# design.net
KiCad netlist of a schematic drawn in Altium Designer
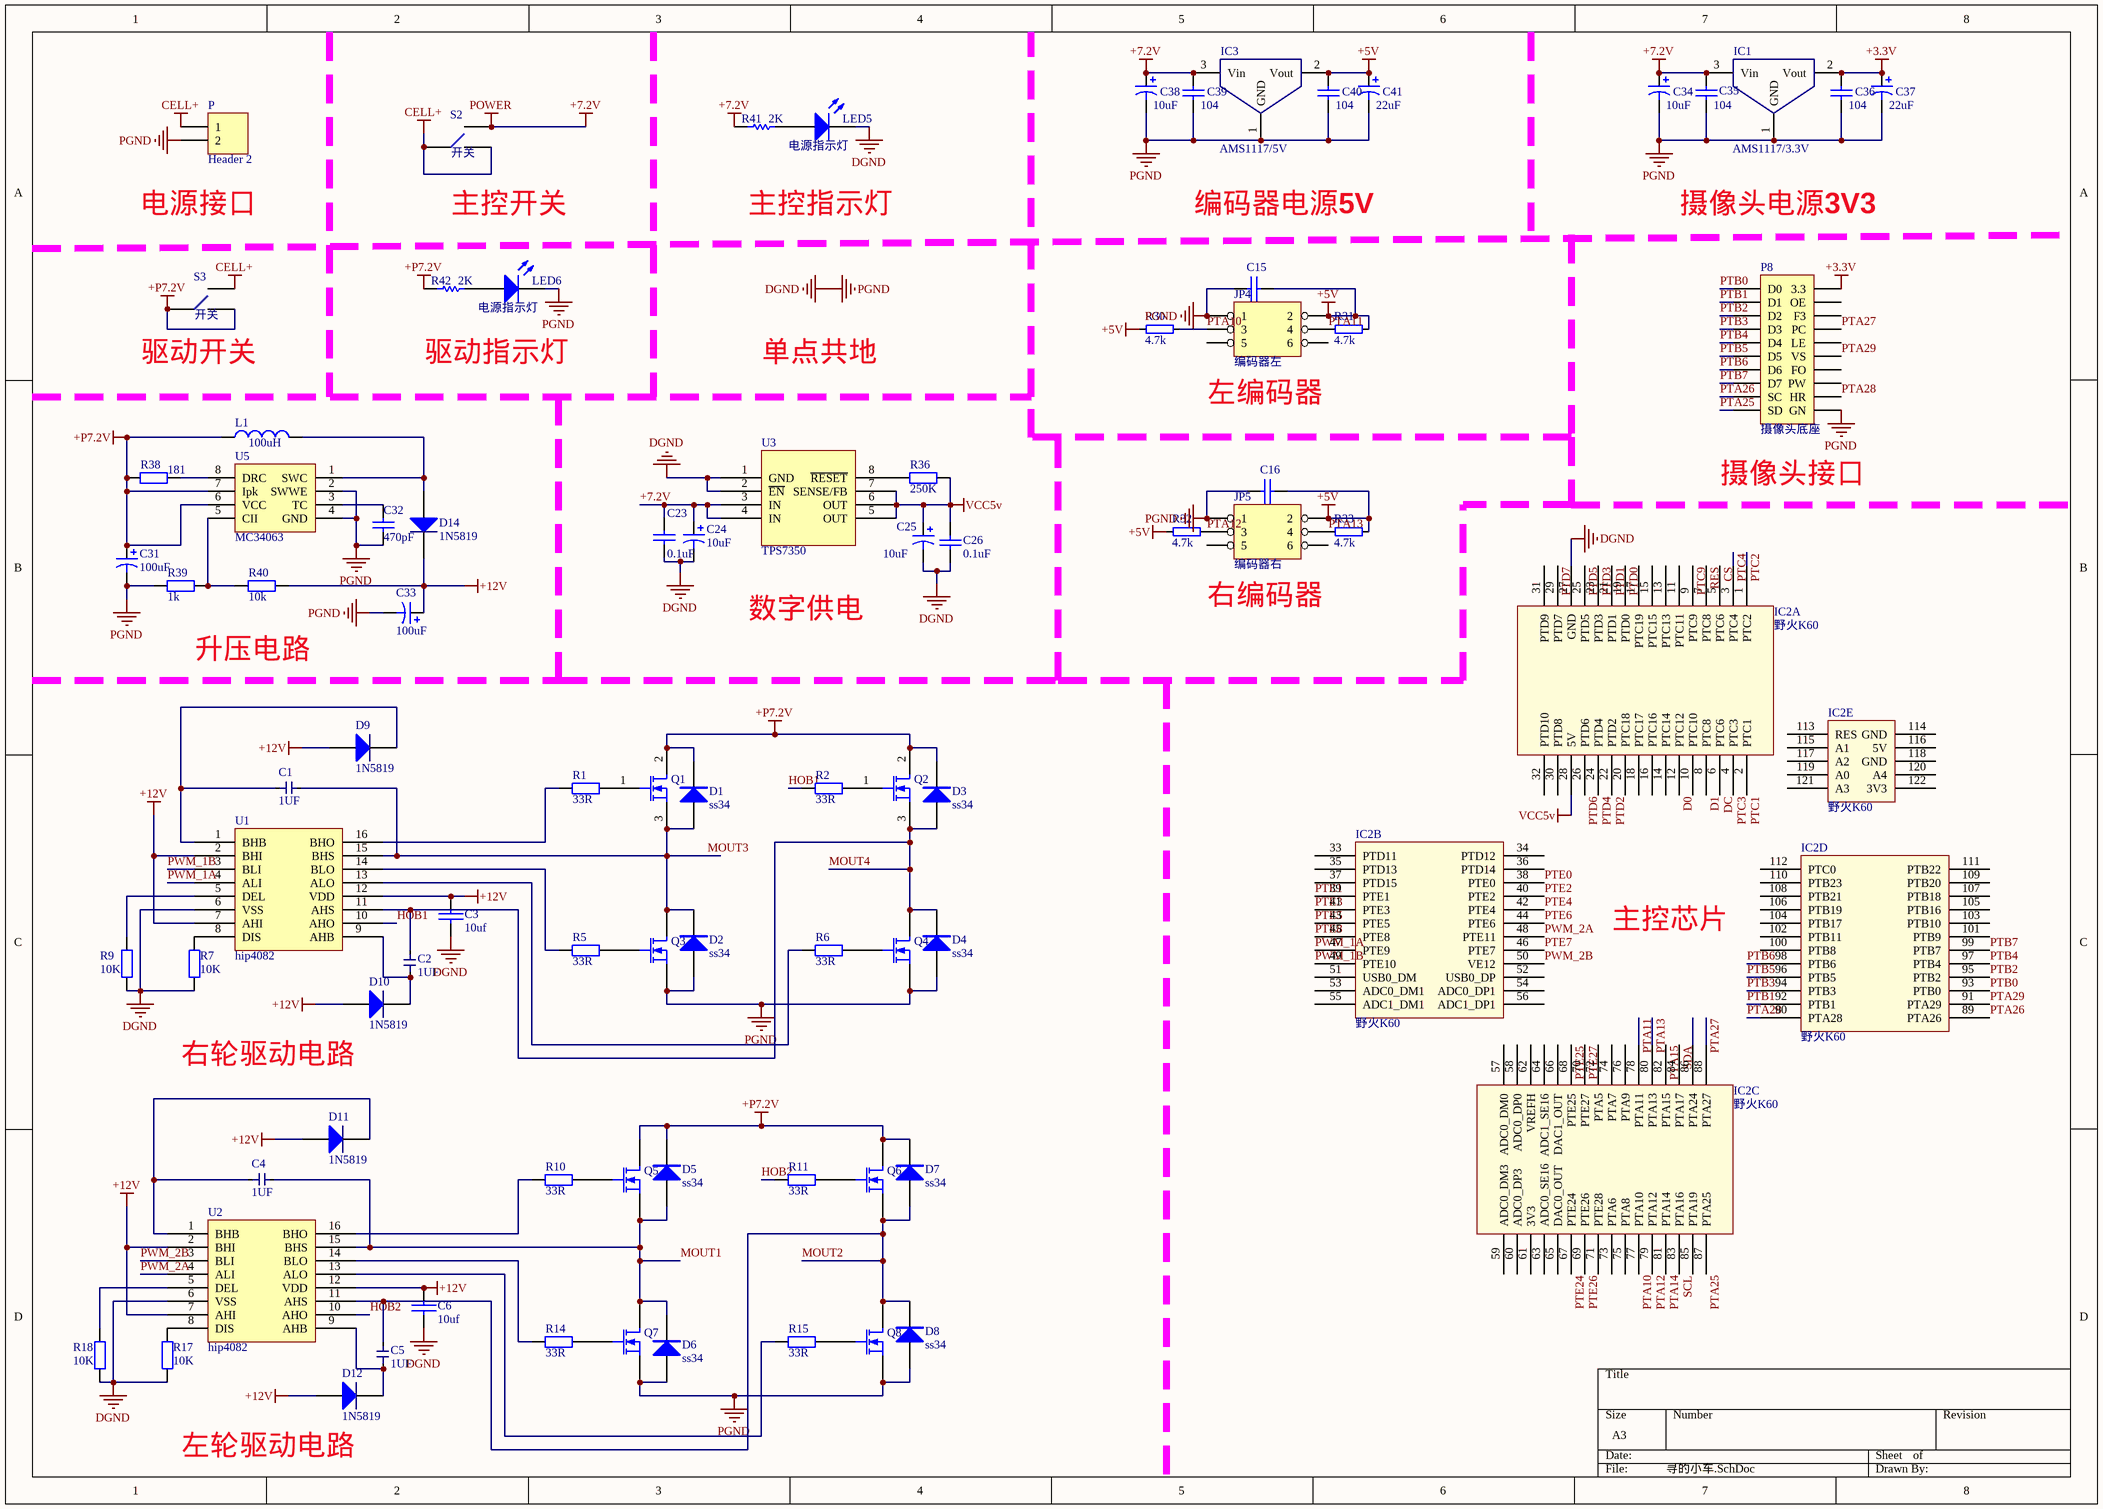
[diagram p0: 寻的小车.SchDoc]

(export (version "E")
  (design (tool "Eeschema 10.0.6"))
  (components
    (comp (ref "C1") (value "1UF") (footprint "0805") (libsource (lib "dx原理图库") (part "电容")))
    (comp (ref "C2") (value "1UF") (footprint "0805") (libsource (lib "dx原理图库") (part "电容")))
    (comp (ref "C3")
      (value "10uf")
      (footprint "0805")
      (description "Capacitor")
      (libsource (lib "电容") (part "普通电容"))
    )
    (comp (ref "C4") (value "1UF") (footprint "0805") (libsource (lib "dx原理图库") (part "电容")))
    (comp (ref "C5") (value "1UF") (footprint "0805") (libsource (lib "dx原理图库") (part "电容")))
    (comp (ref "C6")
      (value "10uf")
      (footprint "0805")
      (description "Capacitor")
      (libsource (lib "电容") (part "普通电容"))
    )
    (comp (ref "C15")
      (value "104")
      (footprint "R0603")
      (description "Capacitor")
      (libsource (lib "电容") (part "普通电容"))
    )
    (comp (ref "C16")
      (value "104")
      (footprint "R0603")
      (description "Capacitor")
      (libsource (lib "电容") (part "普通电容"))
    )
    (comp (ref "C23")
      (value "0.1uF")
      (footprint "R0603")
      (fields (field (name "Comment") "CAPACITY"))
      (libsource (lib "Luo") (part "CAP_0603"))
    )
    (comp (ref "C24")
      (value "10uF")
      (footprint "0805")
      (description "Polarized Capacitor (Surface Mount)")
      (fields (field (name "Comment") "Cap Pol3") (field (name "PUBLISHER") "Altium Limited"))
      (libsource (lib "Miscellaneous Devices") (part "Cap Pol3"))
    )
    (comp (ref "C25")
      (value "10uF")
      (footprint "1206C")
      (fields (field (name "Comment") "CAP  Pol"))
      (libsource (lib "Luo") (part "CAP  Pol"))
    )
    (comp (ref "C26")
      (value "0.1uF")
      (footprint "R0603")
      (fields (field (name "Comment") "CAPACITY"))
      (libsource (lib "Luo") (part "CAP_0603"))
    )
    (comp (ref "C31")
      (value "100uF")
      (footprint "10UF")
      (fields (field (name "Comment") "CAP  Pol"))
      (libsource (lib "Luo") (part "CAP  Pol"))
    )
    (comp (ref "C32")
      (value "470pF")
      (footprint "0805小贴片")
      (fields (field (name "Comment") "CAPACITY"))
      (libsource (lib "Luo") (part "CAP_0805"))
    )
    (comp (ref "C33")
      (value "100uF")
      (footprint "2512")
      (fields (field (name "Comment") "CAP  Pol"))
      (libsource (lib "Luo") (part "CAP  Pol"))
    )
    (comp (ref "C34")
      (value "10uF")
      (footprint "0805")
      (description "Polarized Capacitor (Radial)")
      (fields (field (name "Comment") "Cap Pol1") (field (name "PUBLISHER") "Altium Limited"))
      (libsource (lib "Miscellaneous Devices") (part "Cap Pol1"))
    )
    (comp (ref "C35")
      (value "104")
      (footprint "CAP_0805")
      (description "Capacitor")
      (fields (field (name "Comment") "Cap") (field (name "PUBLISHER") "Altium Limited"))
      (libsource (lib "Miscellaneous Devices") (part "Cap"))
    )
    (comp (ref "C36")
      (value "104")
      (footprint "CAP_0805")
      (description "Capacitor")
      (fields (field (name "Comment") "Cap") (field (name "PUBLISHER") "Altium Limited"))
      (libsource (lib "Miscellaneous Devices") (part "Cap"))
    )
    (comp (ref "C37")
      (value "22uF")
      (footprint "1206C")
      (description "Polarized Capacitor (Radial)")
      (fields (field (name "Comment") "Cap Pol1") (field (name "PUBLISHER") "Altium Limited"))
      (libsource (lib "Miscellaneous Devices") (part "Cap Pol1"))
    )
    (comp (ref "C38")
      (value "10uF")
      (footprint "0805")
      (description "Polarized Capacitor (Radial)")
      (fields (field (name "Comment") "Cap Pol1") (field (name "PUBLISHER") "Altium Limited"))
      (libsource (lib "Miscellaneous Devices") (part "Cap Pol1"))
    )
    (comp (ref "C39")
      (value "104")
      (footprint "CAP_0805")
      (description "Capacitor")
      (fields (field (name "Comment") "Cap") (field (name "PUBLISHER") "Altium Limited"))
      (libsource (lib "Miscellaneous Devices") (part "Cap"))
    )
    (comp (ref "C40")
      (value "104")
      (footprint "CAP_0805")
      (description "Capacitor")
      (fields (field (name "Comment") "Cap") (field (name "PUBLISHER") "Altium Limited"))
      (libsource (lib "Miscellaneous Devices") (part "Cap"))
    )
    (comp (ref "C41")
      (value "22uF")
      (footprint "1206C")
      (description "Polarized Capacitor (Radial)")
      (fields (field (name "Comment") "Cap Pol1") (field (name "PUBLISHER") "Altium Limited"))
      (libsource (lib "Miscellaneous Devices") (part "Cap Pol1"))
    )
    (comp (ref "D1") (value "ss34") (footprint "SS14") (libsource (lib "常用元件库") (part "DIODE")))
    (comp (ref "D2") (value "ss34") (footprint "SS14") (libsource (lib "常用元件库") (part "DIODE")))
    (comp (ref "D3") (value "ss34") (footprint "SS14") (libsource (lib "常用元件库") (part "DIODE")))
    (comp (ref "D4") (value "ss34") (footprint "SS14") (libsource (lib "常用元件库") (part "DIODE")))
    (comp (ref "D5") (value "ss34") (footprint "SS14") (libsource (lib "常用元件库") (part "DIODE")))
    (comp (ref "D6") (value "ss34") (footprint "SS14") (libsource (lib "常用元件库") (part "DIODE")))
    (comp (ref "D7") (value "ss34") (footprint "SS14") (libsource (lib "常用元件库") (part "DIODE")))
    (comp (ref "D8") (value "ss34") (footprint "SS14") (libsource (lib "常用元件库") (part "DIODE")))
    (comp (ref "D9") (value "1N5819") (footprint "SS14") (libsource (lib "Luo") (part "1N5819")))
    (comp (ref "D10") (value "1N5819") (footprint "SS14") (libsource (lib "Luo") (part "1N5819")))
    (comp (ref "D11") (value "1N5819") (footprint "SS14") (libsource (lib "Luo") (part "1N5819")))
    (comp (ref "D12") (value "1N5819") (footprint "SS14") (libsource (lib "Luo") (part "1N5819")))
    (comp (ref "D14") (value "1N5819") (footprint "SS14") (libsource (lib "Luo") (part "1N5819")))
    (comp (ref "IC1")
      (value "AMS1117/3.3V")
      (footprint "SOT_223")
      (libsource (lib "Power_IC") (part "AMS1117"))
    )
    (comp (ref "IC2") (value "野火K60") (footprint "mk60FN") (libsource (lib "Mcu_IC") (part "野火K60")))
    (comp (ref "IC3")
      (value "AMS1117/5V")
      (footprint "SOT_223")
      (libsource (lib "Power_IC") (part "AMS1117"))
    )
    (comp (ref "JP4") (value "编码器左") (footprint "HDR2X3") (libsource (lib "杂元件库") (part "HEADER 3X2")))
    (comp (ref "JP5") (value "编码器右") (footprint "HDR2X3") (libsource (lib "杂元件库") (part "HEADER 3X2")))
    (comp (ref "L1")
      (value "100uH")
      (footprint "小贴片电感")
      (description "Inductor")
      (fields (field (name "PUBLISHER") "Altium Limited"))
      (libsource (lib "Luo") (part "Inductor"))
    )
    (comp (ref "LED5")
      (value "电源指示灯")
      (footprint "0603D")
      (description "Typical INFRARED GaAs LED")
      (fields (field (name "PUBLISHER") "Altium Limited"))
      (libsource (lib "Miscellaneous Devices") (part "LED0"))
    )
    (comp (ref "LED6")
      (value "电源指示灯")
      (footprint "0603D")
      (description "Typical INFRARED GaAs LED")
      (fields (field (name "PUBLISHER") "Altium Limited"))
      (libsource (lib "Miscellaneous Devices") (part "LED0"))
    )
    (comp (ref "P")
      (value "Header 2")
      (footprint "T(G)")
      (description "Header, 2-Pin")
      (fields (field (name "PUBLISHER") "Altium Limited"))
      (libsource (lib "Miscellaneous Connectors") (part "Header 2"))
    )
    (comp (ref "P8")
      (value "摄像头底座")
      (footprint "摄像头座")
      (description "Header, 10-Pin, Dual row, Right Angle")
      (fields (field (name "PUBLISHER") "Altium Limited"))
      (libsource (lib "Miscellaneous Connectors") (part "Header 10X2H"))
    )
    (comp (ref "Q1")
      (value "~")
      (footprint "NMOS")
      (description "N-Channel MOSFET")
      (fields (field (name "PUBLISHER") "Altium Limited"))
      (libsource (lib "Luo") (part "MOSFET-N"))
    )
    (comp (ref "Q2")
      (value "IRF3205")
      (footprint "NMOS")
      (description "N-Channel MOSFET")
      (fields (field (name "PUBLISHER") "Altium Limited"))
      (libsource (lib "Luo") (part "MOSFET-N"))
    )
    (comp (ref "Q3")
      (value "IRF3205")
      (footprint "NMOS")
      (description "N-Channel MOSFET")
      (fields (field (name "PUBLISHER") "Altium Limited"))
      (libsource (lib "") (part "MOSFET-N_1"))
    )
    (comp (ref "Q4")
      (value "IRF3205")
      (footprint "NMOS")
      (description "N-Channel MOSFET")
      (fields (field (name "PUBLISHER") "Altium Limited"))
      (libsource (lib "") (part "MOSFET-N_1"))
    )
    (comp (ref "Q5")
      (value "IRF3205")
      (footprint "NMOS")
      (description "N-Channel MOSFET")
      (fields (field (name "PUBLISHER") "Altium Limited"))
      (libsource (lib "") (part "MOSFET-N_1"))
    )
    (comp (ref "Q6")
      (value "IRF3205")
      (footprint "NMOS")
      (description "N-Channel MOSFET")
      (fields (field (name "PUBLISHER") "Altium Limited"))
      (libsource (lib "") (part "MOSFET-N_1"))
    )
    (comp (ref "Q7")
      (value "IRF3205")
      (footprint "NMOS")
      (description "N-Channel MOSFET")
      (fields (field (name "PUBLISHER") "Altium Limited"))
      (libsource (lib "") (part "MOSFET-N_1"))
    )
    (comp (ref "Q8")
      (value "IRF3205")
      (footprint "NMOS")
      (description "N-Channel MOSFET")
      (fields (field (name "PUBLISHER") "Altium Limited"))
      (libsource (lib "") (part "MOSFET-N_1"))
    )
    (comp (ref "R1")
      (value "33R")
      (footprint "0805")
      (fields (field (name "Comment") "RES2_0805"))
      (libsource (lib "Luo") (part "RES2_0805"))
    )
    (comp (ref "R2")
      (value "33R")
      (footprint "0805")
      (fields (field (name "Comment") "RES2_0805"))
      (libsource (lib "Luo") (part "RES2_0805"))
    )
    (comp (ref "R5")
      (value "33R")
      (footprint "0805")
      (fields (field (name "Comment") "RES2_0805"))
      (libsource (lib "Luo") (part "RES2_0805"))
    )
    (comp (ref "R6")
      (value "33R")
      (footprint "0805")
      (fields (field (name "Comment") "RES2_0805"))
      (libsource (lib "Luo") (part "RES2_0805"))
    )
    (comp (ref "R7")
      (value "10K")
      (footprint "R0603")
      (fields (field (name "Comment") "RES2_0805"))
      (libsource (lib "") (part "RES2_0805_1"))
    )
    (comp (ref "R9")
      (value "10K")
      (footprint "R0603")
      (fields (field (name "Comment") "RES2_0603"))
      (libsource (lib "Luo") (part "RES2_0603"))
    )
    (comp (ref "R10")
      (value "33R")
      (footprint "0805")
      (fields (field (name "Comment") "RES2_0805"))
      (libsource (lib "Luo") (part "RES2_0805"))
    )
    (comp (ref "R11")
      (value "33R")
      (footprint "0805")
      (fields (field (name "Comment") "RES2_0805"))
      (libsource (lib "Luo") (part "RES2_0805"))
    )
    (comp (ref "R14")
      (value "33R")
      (footprint "0805")
      (fields (field (name "Comment") "RES2_0805"))
      (libsource (lib "Luo") (part "RES2_0805"))
    )
    (comp (ref "R15")
      (value "33R")
      (footprint "0805")
      (fields (field (name "Comment") "RES2_0805"))
      (libsource (lib "Luo") (part "RES2_0805"))
    )
    (comp (ref "R17")
      (value "10K")
      (footprint "R0603")
      (fields (field (name "Comment") "RES2_0805"))
      (libsource (lib "") (part "RES2_0805_1"))
    )
    (comp (ref "R18")
      (value "10K")
      (footprint "R0603")
      (fields (field (name "Comment") "RES2_0603"))
      (libsource (lib "Luo") (part "RES2_0603"))
    )
    (comp (ref "R30") (value "4.7k") (footprint "R0603") (libsource (lib "电阻") (part "RES")))
    (comp (ref "R31") (value "4.7k") (footprint "R0603") (libsource (lib "电阻") (part "RES")))
    (comp (ref "R32") (value "4.7k") (footprint "R0603") (libsource (lib "电阻") (part "RES")))
    (comp (ref "R33") (value "4.7k") (footprint "R0603") (libsource (lib "电阻") (part "RES")))
    (comp (ref "R36")
      (value "250K")
      (footprint "0805")
      (fields (field (name "Comment") "RES2_0805"))
      (libsource (lib "Luo") (part "RES2_0805"))
    )
    (comp (ref "R38")
      (value "181")
      (footprint "R0603")
      (fields (field (name "Comment") "RES2_0805"))
      (libsource (lib "Luo") (part "RES2_0805"))
    )
    (comp (ref "R39")
      (value "1k")
      (footprint "R0603")
      (fields (field (name "Comment") "RES2_0805"))
      (libsource (lib "Luo") (part "RES2_0805"))
    )
    (comp (ref "R40")
      (value "10k")
      (footprint "R0603")
      (fields (field (name "Comment") "RES2_0805"))
      (libsource (lib "") (part "RES2_0805_2"))
    )
    (comp (ref "R41")
      (value "2K")
      (footprint "RES_0805")
      (description "Resistor")
      (fields (field (name "Comment") "Res1") (field (name "PUBLISHER") "Altium Limited"))
      (libsource (lib "Miscellaneous Devices") (part "Res1"))
    )
    (comp (ref "R42")
      (value "2K")
      (footprint "RES_0805")
      (description "Resistor")
      (fields (field (name "Comment") "Res1") (field (name "PUBLISHER") "Altium Limited"))
      (libsource (lib "Miscellaneous Devices") (part "Res1"))
    )
    (comp (ref "S2") (value "开关") (footprint "扭头开关") (libsource (lib "lr7843_new") (part "slide_switch")))
    (comp (ref "S3") (value "开关") (footprint "扭头开关") (libsource (lib "lr7843_new") (part "slide_switch")))
    (comp (ref "U1") (value "hip4082") (footprint "SO16NB") (libsource (lib "dx原理图库") (part "hip4082")))
    (comp (ref "U2") (value "hip4082") (footprint "SO16NB") (libsource (lib "dx原理图库") (part "hip4082")))
    (comp (ref "U3")
      (value "TPS7350")
      (footprint "SOP_8")
      (description "This is a power comnonet")
      (libsource (lib "LFB") (part "TPS7350"))
    )
    (comp (ref "U5") (value "MC34063") (footprint "SO8") (libsource (lib "Luo") (part "MC34063")))
  )
  (nets
    (net (code "1") (name "+3.3V") (class "Default")
      (node (ref "C36") (pin "2") (pinfunction "2_2") (pintype "passive"))
      (node (ref "C37") (pin "1") (pinfunction "1_1") (pintype "passive"))
      (node (ref "IC1") (pin "2") (pinfunction "Vout_2") (pintype "passive"))
      (node (ref "P8") (pin "2") (pinfunction "3.3_2") (pintype "passive"))
    )
    (net (code "2") (name "+5V") (class "Default")
      (node (ref "C15") (pin "2") (pinfunction "2_2") (pintype "passive"))
      (node (ref "C16") (pin "2") (pinfunction "2_2") (pintype "passive"))
      (node (ref "C40") (pin "2") (pinfunction "2_2") (pintype "passive"))
      (node (ref "C41") (pin "1") (pinfunction "1_1") (pintype "passive"))
      (node (ref "IC3") (pin "2") (pinfunction "Vout_2") (pintype "passive"))
      (node (ref "JP4") (pin "2") (pinfunction "2_2") (pintype "passive"))
      (node (ref "JP5") (pin "2") (pinfunction "2_2") (pintype "passive"))
      (node (ref "R30") (pin "1") (pinfunction "1_1") (pintype "passive"))
      (node (ref "R31") (pin "2") (pinfunction "2_2") (pintype "passive"))
      (node (ref "R32") (pin "1") (pinfunction "1_1") (pintype "passive"))
      (node (ref "R33") (pin "2") (pinfunction "2_2") (pintype "passive"))
    )
    (net (code "3") (name "+7.2V") (class "Default")
      (node (ref "C23") (pin "2") (pinfunction "2_2") (pintype "passive"))
      (node (ref "C24") (pin "1") (pinfunction "1_1") (pintype "passive"))
      (node (ref "C34") (pin "1") (pinfunction "1_1") (pintype "passive"))
      (node (ref "C35") (pin "2") (pinfunction "2_2") (pintype "passive"))
      (node (ref "C38") (pin "1") (pinfunction "1_1") (pintype "passive"))
      (node (ref "C39") (pin "2") (pinfunction "2_2") (pintype "passive"))
      (node (ref "IC1") (pin "3") (pinfunction "Vin_3") (pintype "passive"))
      (node (ref "IC3") (pin "3") (pinfunction "Vin_3") (pintype "passive"))
      (node (ref "R41") (pin "2") (pinfunction "2_2") (pintype "passive"))
      (node (ref "S2") (pin "2") (pinfunction "2_2") (pintype "passive"))
      (node (ref "U3") (pin "3") (pinfunction "IN_3") (pintype "passive"))
      (node (ref "U3") (pin "4") (pinfunction "IN_4") (pintype "passive"))
    )
    (net (code "4") (name "+12V") (class "Default")
      (node (ref "C3") (pin "1") (pinfunction "1_1") (pintype "passive"))
      (node (ref "C33") (pin "1") (pinfunction "1_1") (pintype "passive"))
      (node (ref "C6") (pin "1") (pinfunction "1_1") (pintype "passive"))
      (node (ref "D10") (pin "1") (pinfunction "A_1") (pintype "passive"))
      (node (ref "D11") (pin "1") (pinfunction "A_1") (pintype "passive"))
      (node (ref "D12") (pin "1") (pinfunction "A_1") (pintype "passive"))
      (node (ref "D14") (pin "2") (pinfunction "K_2") (pintype "passive"))
      (node (ref "D9") (pin "1") (pinfunction "A_1") (pintype "passive"))
      (node (ref "R40") (pin "1") (pinfunction "1_1") (pintype "passive"))
      (node (ref "U1") (pin "12") (pinfunction "VDD_12") (pintype "passive"))
      (node (ref "U1") (pin "2") (pinfunction "BHI_2") (pintype "passive"))
      (node (ref "U1") (pin "7") (pinfunction "AHI_7") (pintype "passive"))
      (node (ref "U2") (pin "12") (pinfunction "VDD_12") (pintype "passive"))
      (node (ref "U2") (pin "2") (pinfunction "BHI_2") (pintype "passive"))
      (node (ref "U2") (pin "7") (pinfunction "AHI_7") (pintype "passive"))
    )
    (net (code "5") (name "+P7.2V") (class "Default")
      (node (ref "C31") (pin "1") (pinfunction "1_1") (pintype "passive"))
      (node (ref "D1") (pin "K") (pinfunction "K_K") (pintype "passive"))
      (node (ref "D3") (pin "K") (pinfunction "K_K") (pintype "passive"))
      (node (ref "D5") (pin "K") (pinfunction "K_K") (pintype "passive"))
      (node (ref "D7") (pin "K") (pinfunction "K_K") (pintype "passive"))
      (node (ref "L1") (pin "1") (pinfunction "1_1") (pintype "passive"))
      (node (ref "Q1") (pin "2") (pinfunction "D_2") (pintype "passive"))
      (node (ref "Q2") (pin "2") (pinfunction "D_2") (pintype "passive"))
      (node (ref "Q5") (pin "2") (pinfunction "D_2") (pintype "passive"))
      (node (ref "Q6") (pin "2") (pinfunction "D_2") (pintype "passive"))
      (node (ref "R38") (pin "1") (pinfunction "1_1") (pintype "passive"))
      (node (ref "R42") (pin "2") (pinfunction "2_2") (pintype "passive"))
      (node (ref "S3") (pin "1") (pinfunction "1_1") (pintype "passive"))
      (node (ref "S3") (pin "3") (pinfunction "3_3") (pintype "passive"))
      (node (ref "U5") (pin "6") (pinfunction "VCC_6") (pintype "passive"))
      (node (ref "U5") (pin "7") (pinfunction "Ipk_7") (pintype "passive"))
    )
    (net (code "6") (name "/CS") (class "Default")
      (node (ref "IC2") (pin "5") (pinfunction "PTC6_5") (pintype "passive"))
    )
    (net (code "7") (name "/D0") (class "Default")
      (node (ref "IC2") (pin "12") (pinfunction "PTC12_12") (pintype "passive"))
    )
    (net (code "8") (name "/D1") (class "Default")
      (node (ref "IC2") (pin "8") (pinfunction "PTC8_8") (pintype "passive"))
    )
    (net (code "9") (name "/DC") (class "Default")
      (node (ref "IC2") (pin "6") (pinfunction "PTC6_6") (pintype "passive"))
    )
    (net (code "10") (name "/HOB1") (class "Default")
      (node (ref "R2") (pin "1") (pinfunction "1_1") (pintype "passive"))
      (node (ref "U1") (pin "10") (pinfunction "AHO_10") (pintype "passive"))
    )
    (net (code "11") (name "/HOB2") (class "Default")
      (node (ref "R11") (pin "1") (pinfunction "1_1") (pintype "passive"))
      (node (ref "U2") (pin "10") (pinfunction "AHO_10") (pintype "passive"))
    )
    (net (code "12") (name "/MOUT1") (class "Default")
      (node (ref "C4") (pin "18") (pinfunction "18_18") (pintype "passive"))
      (node (ref "D5") (pin "A") (pinfunction "A_A") (pintype "passive"))
      (node (ref "D6") (pin "K") (pinfunction "K_K") (pintype "passive"))
      (node (ref "Q5") (pin "3") (pinfunction "S_3") (pintype "passive"))
      (node (ref "Q7") (pin "2") (pinfunction "D_2") (pintype "passive"))
      (node (ref "U2") (pin "15") (pinfunction "BHS_15") (pintype "passive"))
    )
    (net (code "13") (name "/MOUT2") (class "Default")
      (node (ref "C5") (pin "18") (pinfunction "18_18") (pintype "passive"))
      (node (ref "D7") (pin "A") (pinfunction "A_A") (pintype "passive"))
      (node (ref "D8") (pin "K") (pinfunction "K_K") (pintype "passive"))
      (node (ref "Q6") (pin "3") (pinfunction "S_3") (pintype "passive"))
      (node (ref "Q8") (pin "2") (pinfunction "D_2") (pintype "passive"))
      (node (ref "U2") (pin "11") (pinfunction "AHS_11") (pintype "passive"))
    )
    (net (code "14") (name "/MOUT3") (class "Default")
      (node (ref "C1") (pin "18") (pinfunction "18_18") (pintype "passive"))
      (node (ref "D1") (pin "A") (pinfunction "A_A") (pintype "passive"))
      (node (ref "D2") (pin "K") (pinfunction "K_K") (pintype "passive"))
      (node (ref "Q1") (pin "3") (pinfunction "S_3") (pintype "passive"))
      (node (ref "Q3") (pin "2") (pinfunction "D_2") (pintype "passive"))
      (node (ref "U1") (pin "15") (pinfunction "BHS_15") (pintype "passive"))
    )
    (net (code "15") (name "/MOUT4") (class "Default")
      (node (ref "C2") (pin "18") (pinfunction "18_18") (pintype "passive"))
      (node (ref "D3") (pin "A") (pinfunction "A_A") (pintype "passive"))
      (node (ref "D4") (pin "K") (pinfunction "K_K") (pintype "passive"))
      (node (ref "Q2") (pin "3") (pinfunction "S_3") (pintype "passive"))
      (node (ref "Q4") (pin "2") (pinfunction "D_2") (pintype "passive"))
      (node (ref "U1") (pin "11") (pinfunction "AHS_11") (pintype "passive"))
    )
    (net (code "16") (name "/PTA10") (class "Default")
      (node (ref "IC2") (pin "77") (pinfunction "PTA10_77") (pintype "passive"))
      (node (ref "JP4") (pin "3") (pinfunction "3_3") (pintype "passive"))
      (node (ref "R30") (pin "2") (pinfunction "2_2") (pintype "passive"))
    )
    (net (code "17") (name "/PTA11") (class "Default")
      (node (ref "IC2") (pin "78") (pinfunction "PTA11_78") (pintype "passive"))
      (node (ref "JP4") (pin "4") (pinfunction "4_4") (pintype "passive"))
      (node (ref "R31") (pin "1") (pinfunction "1_1") (pintype "passive"))
    )
    (net (code "18") (name "/PTA12") (class "Default")
      (node (ref "IC2") (pin "79") (pinfunction "PTA12_79") (pintype "passive"))
      (node (ref "JP5") (pin "3") (pinfunction "3_3") (pintype "passive"))
      (node (ref "R32") (pin "2") (pinfunction "2_2") (pintype "passive"))
    )
    (net (code "19") (name "/PTA13") (class "Default")
      (node (ref "IC2") (pin "80") (pinfunction "PTA13_80") (pintype "passive"))
      (node (ref "JP5") (pin "4") (pinfunction "4_4") (pintype "passive"))
      (node (ref "R33") (pin "1") (pinfunction "1_1") (pintype "passive"))
    )
    (net (code "20") (name "/PTA14") (class "Default")
      (node (ref "IC2") (pin "81") (pinfunction "PTA14_81") (pintype "passive"))
    )
    (net (code "21") (name "/PTA15") (class "Default")
      (node (ref "IC2") (pin "82") (pinfunction "PTA15_82") (pintype "passive"))
    )
    (net (code "22") (name "/PTA25") (class "Default")
      (node (ref "IC2") (pin "87") (pinfunction "PTA25_87") (pintype "passive"))
      (node (ref "P8") (pin "19") (pinfunction "SD_19") (pintype "passive"))
    )
    (net (code "23") (name "/PTA26") (class "Default")
      (node (ref "IC2") (pin "89") (pinfunction "PTA26_89") (pintype "passive"))
      (node (ref "P8") (pin "17") (pinfunction "SC_17") (pintype "passive"))
    )
    (net (code "24") (name "/PTA27") (class "Default")
      (node (ref "IC2") (pin "88") (pinfunction "PTA27_88") (pintype "passive"))
      (node (ref "P8") (pin "8") (pinfunction "PC_8") (pintype "passive"))
    )
    (net (code "25") (name "/PTA28") (class "Default")
      (node (ref "IC2") (pin "90") (pinfunction "PTA28_90") (pintype "passive"))
      (node (ref "P8") (pin "18") (pinfunction "HR_18") (pintype "passive"))
    )
    (net (code "26") (name "/PTA29") (class "Default")
      (node (ref "IC2") (pin "91") (pinfunction "PTA29_91") (pintype "passive"))
      (node (ref "P8") (pin "12") (pinfunction "VS_12") (pintype "passive"))
    )
    (net (code "27") (name "/PTB0") (class "Default")
      (node (ref "IC2") (pin "93") (pinfunction "PTB0_93") (pintype "passive"))
      (node (ref "P8") (pin "1") (pinfunction "D0_1") (pintype "passive"))
    )
    (net (code "28") (name "/PTB1") (class "Default")
      (node (ref "IC2") (pin "92") (pinfunction "PTB1_92") (pintype "passive"))
      (node (ref "P8") (pin "3") (pinfunction "D1_3") (pintype "passive"))
    )
    (net (code "29") (name "/PTB2") (class "Default")
      (node (ref "IC2") (pin "95") (pinfunction "PTB2_95") (pintype "passive"))
      (node (ref "P8") (pin "5") (pinfunction "D2_5") (pintype "passive"))
    )
    (net (code "30") (name "/PTB3") (class "Default")
      (node (ref "IC2") (pin "94") (pinfunction "PTB3_94") (pintype "passive"))
      (node (ref "P8") (pin "7") (pinfunction "D3_7") (pintype "passive"))
    )
    (net (code "31") (name "/PTB4") (class "Default")
      (node (ref "IC2") (pin "97") (pinfunction "PTB4_97") (pintype "passive"))
      (node (ref "P8") (pin "9") (pinfunction "D4_9") (pintype "passive"))
    )
    (net (code "32") (name "/PTB5") (class "Default")
      (node (ref "IC2") (pin "96") (pinfunction "PTB5_96") (pintype "passive"))
      (node (ref "P8") (pin "11") (pinfunction "D5_11") (pintype "passive"))
    )
    (net (code "33") (name "/PTB6") (class "Default")
      (node (ref "IC2") (pin "98") (pinfunction "PTB6_98") (pintype "passive"))
      (node (ref "P8") (pin "13") (pinfunction "D6_13") (pintype "passive"))
    )
    (net (code "34") (name "/PTB7") (class "Default")
      (node (ref "IC2") (pin "99") (pinfunction "PTB7_99") (pintype "passive"))
      (node (ref "P8") (pin "15") (pinfunction "D7_15") (pintype "passive"))
    )
    (net (code "35") (name "/PTC1") (class "Default")
      (node (ref "IC2") (pin "2") (pinfunction "PTC1_2") (pintype "passive"))
    )
    (net (code "36") (name "/PTC2") (class "Default")
      (node (ref "IC2") (pin "1") (pinfunction "PTC2_1") (pintype "passive"))
    )
    (net (code "37") (name "/PTC3") (class "Default")
      (node (ref "IC2") (pin "4") (pinfunction "PTC3_4") (pintype "passive"))
    )
    (net (code "38") (name "/PTC4") (class "Default")
      (node (ref "IC2") (pin "3") (pinfunction "PTC4_3") (pintype "passive"))
    )
    (net (code "39") (name "/PTC9") (class "Default")
      (node (ref "IC2") (pin "9") (pinfunction "PTC9_9") (pintype "passive"))
    )
    (net (code "40") (name "/PTD0") (class "Default")
      (node (ref "IC2") (pin "19") (pinfunction "PTD0_19") (pintype "passive"))
    )
    (net (code "41") (name "/PTD1") (class "Default")
      (node (ref "IC2") (pin "21") (pinfunction "PTD1_21") (pintype "passive"))
    )
    (net (code "42") (name "/PTD2") (class "Default")
      (node (ref "IC2") (pin "22") (pinfunction "PTD2_22") (pintype "passive"))
    )
    (net (code "43") (name "/PTD3") (class "Default")
      (node (ref "IC2") (pin "23") (pinfunction "PTD3_23") (pintype "passive"))
    )
    (net (code "44") (name "/PTD4") (class "Default")
      (node (ref "IC2") (pin "24") (pinfunction "PTD4_24") (pintype "passive"))
    )
    (net (code "45") (name "/PTD5") (class "Default")
      (node (ref "IC2") (pin "25") (pinfunction "PTD5_25") (pintype "passive"))
    )
    (net (code "46") (name "/PTD6") (class "Default")
      (node (ref "IC2") (pin "26") (pinfunction "PTD6_26") (pintype "passive"))
    )
    (net (code "47") (name "/PTD7") (class "Default")
      (node (ref "IC2") (pin "29") (pinfunction "PTD7_29") (pintype "passive"))
    )
    (net (code "48") (name "/PTE0") (class "Default")
      (node (ref "IC2") (pin "38") (pinfunction "PTE0_38") (pintype "passive"))
    )
    (net (code "49") (name "/PTE1") (class "Default")
      (node (ref "IC2") (pin "39") (pinfunction "PTE1_39") (pintype "passive"))
    )
    (net (code "50") (name "/PTE2") (class "Default")
      (node (ref "IC2") (pin "40") (pinfunction "PTE2_40") (pintype "passive"))
    )
    (net (code "51") (name "/PTE3") (class "Default")
      (node (ref "IC2") (pin "41") (pinfunction "PTE3_41") (pintype "passive"))
    )
    (net (code "52") (name "/PTE4") (class "Default")
      (node (ref "IC2") (pin "42") (pinfunction "PTE4_42") (pintype "passive"))
    )
    (net (code "53") (name "/PTE5") (class "Default")
      (node (ref "IC2") (pin "43") (pinfunction "PTE5_43") (pintype "passive"))
    )
    (net (code "54") (name "/PTE6") (class "Default")
      (node (ref "IC2") (pin "44") (pinfunction "PTE6_44") (pintype "passive"))
    )
    (net (code "55") (name "/PTE7") (class "Default")
      (node (ref "IC2") (pin "46") (pinfunction "PTE7_46") (pintype "passive"))
    )
    (net (code "56") (name "/PTE8") (class "Default")
      (node (ref "IC2") (pin "45") (pinfunction "PTE8_45") (pintype "passive"))
    )
    (net (code "57") (name "/PTE24") (class "Default")
      (node (ref "IC2") (pin "67") (pinfunction "PTE24_67") (pintype "passive"))
    )
    (net (code "58") (name "/PTE25") (class "Default")
      (node (ref "IC2") (pin "68") (pinfunction "PTE25_68") (pintype "passive"))
    )
    (net (code "59") (name "/PTE26") (class "Default")
      (node (ref "IC2") (pin "69") (pinfunction "PTE26_69") (pintype "passive"))
    )
    (net (code "60") (name "/PTE27") (class "Default")
      (node (ref "IC2") (pin "70") (pinfunction "PTE27_70") (pintype "passive"))
    )
    (net (code "61") (name "/PWM_1A") (class "Default")
      (node (ref "IC2") (pin "47") (pinfunction "PTE9_47") (pintype "passive"))
      (node (ref "U1") (pin "4") (pinfunction "ALI_4") (pintype "passive"))
    )
    (net (code "62") (name "/PWM_1B") (class "Default")
      (node (ref "IC2") (pin "49") (pinfunction "PTE10_49") (pintype "passive"))
      (node (ref "U1") (pin "3") (pinfunction "BLI_3") (pintype "passive"))
    )
    (net (code "63") (name "/PWM_2A") (class "Default")
      (node (ref "IC2") (pin "48") (pinfunction "PTE11_48") (pintype "passive"))
      (node (ref "U2") (pin "4") (pinfunction "ALI_4") (pintype "passive"))
    )
    (net (code "64") (name "/PWM_2B") (class "Default")
      (node (ref "IC2") (pin "50") (pinfunction "VE12_50") (pintype "passive"))
      (node (ref "U2") (pin "3") (pinfunction "BLI_3") (pintype "passive"))
    )
    (net (code "65") (name "/RES") (class "Default")
      (node (ref "IC2") (pin "7") (pinfunction "PTC8_7") (pintype "passive"))
    )
    (net (code "66") (name "/SCL") (class "Default")
      (node (ref "IC2") (pin "83") (pinfunction "PTA16_83") (pintype "passive"))
    )
    (net (code "67") (name "/SDA") (class "Default")
      (node (ref "IC2") (pin "84") (pinfunction "PTA17_84") (pintype "passive"))
    )
    (net (code "68") (name "CELL+") (class "Default")
      (node (ref "P") (pin "1") (pinfunction "1_1") (pintype "passive"))
      (node (ref "S2") (pin "1") (pinfunction "1_1") (pintype "passive"))
      (node (ref "S2") (pin "3") (pinfunction "3_3") (pintype "passive"))
      (node (ref "S3") (pin "2") (pinfunction "2_2") (pintype "passive"))
    )
    (net (code "69") (name "DGND") (class "Default")
      (node (ref "C15") (pin "1") (pinfunction "1_1") (pintype "passive"))
      (node (ref "C16") (pin "1") (pinfunction "1_1") (pintype "passive"))
      (node (ref "C23") (pin "1") (pinfunction "1_1") (pintype "passive"))
      (node (ref "C24") (pin "2") (pinfunction "2_2") (pintype "passive"))
      (node (ref "C25") (pin "2") (pinfunction "2_2") (pintype "passive"))
      (node (ref "C26") (pin "1") (pinfunction "1_1") (pintype "passive"))
      (node (ref "C3") (pin "2") (pinfunction "2_2") (pintype "passive"))
      (node (ref "C31") (pin "2") (pinfunction "2_2") (pintype "passive"))
      (node (ref "C32") (pin "1") (pinfunction "1_1") (pintype "passive"))
      (node (ref "C33") (pin "2") (pinfunction "2_2") (pintype "passive"))
      (node (ref "C34") (pin "2") (pinfunction "2_2") (pintype "passive"))
      (node (ref "C35") (pin "1") (pinfunction "1_1") (pintype "passive"))
      (node (ref "C36") (pin "1") (pinfunction "1_1") (pintype "passive"))
      (node (ref "C37") (pin "2") (pinfunction "2_2") (pintype "passive"))
      (node (ref "C38") (pin "2") (pinfunction "2_2") (pintype "passive"))
      (node (ref "C39") (pin "1") (pinfunction "1_1") (pintype "passive"))
      (node (ref "C40") (pin "1") (pinfunction "1_1") (pintype "passive"))
      (node (ref "C41") (pin "2") (pinfunction "2_2") (pintype "passive"))
      (node (ref "C6") (pin "2") (pinfunction "2_2") (pintype "passive"))
      (node (ref "D2") (pin "A") (pinfunction "A_A") (pintype "passive"))
      (node (ref "D4") (pin "A") (pinfunction "A_A") (pintype "passive"))
      (node (ref "D6") (pin "A") (pinfunction "A_A") (pintype "passive"))
      (node (ref "D8") (pin "A") (pinfunction "A_A") (pintype "passive"))
      (node (ref "IC1") (pin "1") (pinfunction "GND_1") (pintype "passive"))
      (node (ref "IC2") (pin "27") (pinfunction "GND_27") (pintype "passive"))
      (node (ref "IC3") (pin "1") (pinfunction "GND_1") (pintype "passive"))
      (node (ref "JP4") (pin "1") (pinfunction "1_1") (pintype "passive"))
      (node (ref "JP5") (pin "1") (pinfunction "1_1") (pintype "passive"))
      (node (ref "LED5") (pin "2") (pinfunction "K_2") (pintype "passive"))
      (node (ref "LED6") (pin "2") (pinfunction "K_2") (pintype "passive"))
      (node (ref "P") (pin "2") (pinfunction "2_2") (pintype "passive"))
      (node (ref "P8") (pin "20") (pinfunction "GN_20") (pintype "passive"))
      (node (ref "Q3") (pin "3") (pinfunction "S_3") (pintype "passive"))
      (node (ref "Q4") (pin "3") (pinfunction "S_3") (pintype "passive"))
      (node (ref "Q7") (pin "3") (pinfunction "S_3") (pintype "passive"))
      (node (ref "Q8") (pin "3") (pinfunction "S_3") (pintype "passive"))
      (node (ref "R17") (pin "1") (pinfunction "1_1") (pintype "passive"))
      (node (ref "R18") (pin "2") (pinfunction "2_2") (pintype "passive"))
      (node (ref "R39") (pin "1") (pinfunction "1_1") (pintype "passive"))
      (node (ref "R7") (pin "1") (pinfunction "1_1") (pintype "passive"))
      (node (ref "R9") (pin "2") (pinfunction "2_2") (pintype "passive"))
      (node (ref "U1") (pin "6") (pinfunction "VSS_6") (pintype "passive"))
      (node (ref "U2") (pin "6") (pinfunction "VSS_6") (pintype "passive"))
      (node (ref "U3") (pin "1") (pinfunction "GND_1") (pintype "passive"))
      (node (ref "U3") (pin "2") (pinfunction "~{EN}_2") (pintype "passive"))
      (node (ref "U5") (pin "2") (pinfunction "SWWE_2") (pintype "passive"))
      (node (ref "U5") (pin "4") (pinfunction "GND_4") (pintype "passive"))
    )
    (net (code "70") (name "Net-(D9-K)") (class "Default")
      (node (ref "C1") (pin "17") (pintype "passive"))
      (node (ref "D9") (pin "2") (pinfunction "K_2") (pintype "passive"))
      (node (ref "U1") (pin "1") (pinfunction "BHB_1") (pintype "passive"))
    )
    (net (code "71") (name "Net-(D10-K)") (class "Default")
      (node (ref "C2") (pin "17") (pintype "passive"))
      (node (ref "D10") (pin "2") (pinfunction "K_2") (pintype "passive"))
      (node (ref "U1") (pin "9") (pinfunction "AHB_9") (pintype "passive"))
    )
    (net (code "72") (name "Net-(D11-K)") (class "Default")
      (node (ref "C4") (pin "17") (pintype "passive"))
      (node (ref "D11") (pin "2") (pinfunction "K_2") (pintype "passive"))
      (node (ref "U2") (pin "1") (pinfunction "BHB_1") (pintype "passive"))
    )
    (net (code "73") (name "Net-(D12-K)") (class "Default")
      (node (ref "C5") (pin "17") (pintype "passive"))
      (node (ref "D12") (pin "2") (pinfunction "K_2") (pintype "passive"))
      (node (ref "U2") (pin "9") (pinfunction "AHB_9") (pintype "passive"))
    )
    (net (code "74") (name "Net-(D14-A)") (class "Default")
      (node (ref "D14") (pin "1") (pinfunction "A_1") (pintype "passive"))
      (node (ref "L1") (pin "2") (pinfunction "2_2") (pintype "passive"))
      (node (ref "U5") (pin "1") (pinfunction "SWC_1") (pintype "passive"))
    )
    (net (code "75") (name "Net-(LED5-A)") (class "Default")
      (node (ref "LED5") (pin "1") (pinfunction "A_1") (pintype "passive"))
      (node (ref "R41") (pin "1") (pinfunction "1_1") (pintype "passive"))
    )
    (net (code "76") (name "Net-(LED6-A)") (class "Default")
      (node (ref "LED6") (pin "1") (pinfunction "A_1") (pintype "passive"))
      (node (ref "R42") (pin "1") (pinfunction "1_1") (pintype "passive"))
    )
    (net (code "77") (name "Net-(Q1-G)") (class "Default")
      (node (ref "Q1") (pin "1") (pinfunction "G_1") (pintype "passive"))
      (node (ref "R1") (pin "2") (pinfunction "2_2") (pintype "passive"))
    )
    (net (code "78") (name "Net-(Q2-G)") (class "Default")
      (node (ref "Q2") (pin "1") (pinfunction "G_1") (pintype "passive"))
      (node (ref "R2") (pin "2") (pinfunction "2_2") (pintype "passive"))
    )
    (net (code "79") (name "Net-(Q3-G)") (class "Default")
      (node (ref "Q3") (pin "1") (pinfunction "G_1") (pintype "passive"))
      (node (ref "R5") (pin "2") (pinfunction "2_2") (pintype "passive"))
    )
    (net (code "80") (name "Net-(Q4-G)") (class "Default")
      (node (ref "Q4") (pin "1") (pinfunction "G_1") (pintype "passive"))
      (node (ref "R6") (pin "2") (pinfunction "2_2") (pintype "passive"))
    )
    (net (code "81") (name "Net-(Q5-G)") (class "Default")
      (node (ref "Q5") (pin "1") (pinfunction "G_1") (pintype "passive"))
      (node (ref "R10") (pin "2") (pinfunction "2_2") (pintype "passive"))
    )
    (net (code "82") (name "Net-(Q6-G)") (class "Default")
      (node (ref "Q6") (pin "1") (pinfunction "G_1") (pintype "passive"))
      (node (ref "R11") (pin "2") (pinfunction "2_2") (pintype "passive"))
    )
    (net (code "83") (name "Net-(Q7-G)") (class "Default")
      (node (ref "Q7") (pin "1") (pinfunction "G_1") (pintype "passive"))
      (node (ref "R14") (pin "2") (pinfunction "2_2") (pintype "passive"))
    )
    (net (code "84") (name "Net-(Q8-G)") (class "Default")
      (node (ref "Q8") (pin "1") (pinfunction "G_1") (pintype "passive"))
      (node (ref "R15") (pin "2") (pinfunction "2_2") (pintype "passive"))
    )
    (net (code "85") (name "Net-(U1-ALO)") (class "Default")
      (node (ref "R6") (pin "1") (pinfunction "1_1") (pintype "passive"))
      (node (ref "U1") (pin "13") (pinfunction "ALO_13") (pintype "passive"))
    )
    (net (code "86") (name "Net-(U1-BHO)") (class "Default")
      (node (ref "R1") (pin "1") (pinfunction "1_1") (pintype "passive"))
      (node (ref "U1") (pin "16") (pinfunction "BHO_16") (pintype "passive"))
    )
    (net (code "87") (name "Net-(U1-BLO)") (class "Default")
      (node (ref "R5") (pin "1") (pinfunction "1_1") (pintype "passive"))
      (node (ref "U1") (pin "14") (pinfunction "BLO_14") (pintype "passive"))
    )
    (net (code "88") (name "Net-(U1-DEL)") (class "Default")
      (node (ref "R9") (pin "1") (pinfunction "1_1") (pintype "passive"))
      (node (ref "U1") (pin "5") (pinfunction "DEL_5") (pintype "passive"))
    )
    (net (code "89") (name "Net-(U1-DIS)") (class "Default")
      (node (ref "R7") (pin "2") (pinfunction "2_2") (pintype "passive"))
      (node (ref "U1") (pin "8") (pinfunction "DIS_8") (pintype "passive"))
    )
    (net (code "90") (name "Net-(U2-ALO)") (class "Default")
      (node (ref "R15") (pin "1") (pinfunction "1_1") (pintype "passive"))
      (node (ref "U2") (pin "13") (pinfunction "ALO_13") (pintype "passive"))
    )
    (net (code "91") (name "Net-(U2-BHO)") (class "Default")
      (node (ref "R10") (pin "1") (pinfunction "1_1") (pintype "passive"))
      (node (ref "U2") (pin "16") (pinfunction "BHO_16") (pintype "passive"))
    )
    (net (code "92") (name "Net-(U2-BLO)") (class "Default")
      (node (ref "R14") (pin "1") (pinfunction "1_1") (pintype "passive"))
      (node (ref "U2") (pin "14") (pinfunction "BLO_14") (pintype "passive"))
    )
    (net (code "93") (name "Net-(U2-DEL)") (class "Default")
      (node (ref "R18") (pin "1") (pinfunction "1_1") (pintype "passive"))
      (node (ref "U2") (pin "5") (pinfunction "DEL_5") (pintype "passive"))
    )
    (net (code "94") (name "Net-(U2-DIS)") (class "Default")
      (node (ref "R17") (pin "2") (pinfunction "2_2") (pintype "passive"))
      (node (ref "U2") (pin "8") (pinfunction "DIS_8") (pintype "passive"))
    )
    (net (code "95") (name "Net-(U3-~{RESET})") (class "Default")
      (node (ref "R36") (pin "1") (pinfunction "1_1") (pintype "passive"))
      (node (ref "U3") (pin "8") (pinfunction "~{RESET}_8") (pintype "passive"))
    )
    (net (code "96") (name "Net-(U5-CII)") (class "Default")
      (node (ref "R39") (pin "2") (pinfunction "2_2") (pintype "passive"))
      (node (ref "R40") (pin "2") (pinfunction "2_2") (pintype "passive"))
      (node (ref "U5") (pin "5") (pinfunction "CII_5") (pintype "passive"))
    )
    (net (code "97") (name "Net-(U5-DRC)") (class "Default")
      (node (ref "R38") (pin "2") (pinfunction "2_2") (pintype "passive"))
      (node (ref "U5") (pin "8") (pinfunction "DRC_8") (pintype "passive"))
    )
    (net (code "98") (name "Net-(U5-TC)") (class "Default")
      (node (ref "C32") (pin "2") (pinfunction "2_2") (pintype "passive"))
      (node (ref "U5") (pin "3") (pinfunction "TC_3") (pintype "passive"))
    )
    (net (code "99") (name "VCC5v") (class "Default")
      (node (ref "C25") (pin "1") (pinfunction "1_1") (pintype "passive"))
      (node (ref "C26") (pin "2") (pinfunction "2_2") (pintype "passive"))
      (node (ref "IC2") (pin "28") (pinfunction "5V_28") (pintype "passive"))
      (node (ref "R36") (pin "2") (pinfunction "2_2") (pintype "passive"))
      (node (ref "U3") (pin "5") (pinfunction "OUT_5") (pintype "passive"))
      (node (ref "U3") (pin "6") (pinfunction "OUT_6") (pintype "passive"))
      (node (ref "U3") (pin "7") (pinfunction "SENSE/FB_7") (pintype "passive"))
    )
    (net (code "100") (name "unconnected-(IC2A-PTC10-Pad10)") (class "Default")
      (node (ref "IC2") (pin "10") (pinfunction "PTC10_10") (pintype "passive"))
    )
    (net (code "101") (name "unconnected-(IC2A-PTC11-Pad11)") (class "Default")
      (node (ref "IC2") (pin "11") (pinfunction "PTC11_11") (pintype "passive"))
    )
    (net (code "102") (name "unconnected-(IC2A-PTC13-Pad13)") (class "Default")
      (node (ref "IC2") (pin "13") (pinfunction "PTC13_13") (pintype "passive"))
    )
    (net (code "103") (name "unconnected-(IC2A-PTC14-Pad14)") (class "Default")
      (node (ref "IC2") (pin "14") (pinfunction "PTC14_14") (pintype "passive"))
    )
    (net (code "104") (name "unconnected-(IC2A-PTC15-Pad15)") (class "Default")
      (node (ref "IC2") (pin "15") (pinfunction "PTC15_15") (pintype "passive"))
    )
    (net (code "105") (name "unconnected-(IC2A-PTC16-Pad16)") (class "Default")
      (node (ref "IC2") (pin "16") (pinfunction "PTC16_16") (pintype "passive"))
    )
    (net (code "106") (name "unconnected-(IC2A-PTC17-Pad18)") (class "Default")
      (node (ref "IC2") (pin "18") (pinfunction "PTC17_18") (pintype "passive"))
    )
    (net (code "107") (name "unconnected-(IC2A-PTC18-Pad20)") (class "Default")
      (node (ref "IC2") (pin "20") (pinfunction "PTC18_20") (pintype "passive"))
    )
    (net (code "108") (name "unconnected-(IC2A-PTC19-Pad17)") (class "Default")
      (node (ref "IC2") (pin "17") (pinfunction "PTC19_17") (pintype "passive"))
    )
    (net (code "109") (name "unconnected-(IC2A-PTD8-Pad30)") (class "Default")
      (node (ref "IC2") (pin "30") (pinfunction "PTD8_30") (pintype "passive"))
    )
    (net (code "110") (name "unconnected-(IC2A-PTD9-Pad31)") (class "Default")
      (node (ref "IC2") (pin "31") (pinfunction "PTD9_31") (pintype "passive"))
    )
    (net (code "111") (name "unconnected-(IC2A-PTD10-Pad32)") (class "Default")
      (node (ref "IC2") (pin "32") (pinfunction "PTD10_32") (pintype "passive"))
    )
    (net (code "112") (name "unconnected-(IC2B-ADC0_DM1-Pad53)") (class "Default")
      (node (ref "IC2") (pin "53") (pinfunction "ADC0_DM1_53") (pintype "passive"))
    )
    (net (code "113") (name "unconnected-(IC2B-ADC0_DP1-Pad54)") (class "Default")
      (node (ref "IC2") (pin "54") (pinfunction "ADC0_DP1_54") (pintype "passive"))
    )
    (net (code "114") (name "unconnected-(IC2B-ADC1_DM1-Pad55)") (class "Default")
      (node (ref "IC2") (pin "55") (pinfunction "ADC1_DM1_55") (pintype "passive"))
    )
    (net (code "115") (name "unconnected-(IC2B-ADC1_DP1-Pad56)") (class "Default")
      (node (ref "IC2") (pin "56") (pinfunction "ADC1_DP1_56") (pintype "passive"))
    )
    (net (code "116") (name "unconnected-(IC2B-PTD11-Pad33)") (class "Default")
      (node (ref "IC2") (pin "33") (pinfunction "PTD11_33") (pintype "passive"))
    )
    (net (code "117") (name "unconnected-(IC2B-PTD12-Pad34)") (class "Default")
      (node (ref "IC2") (pin "34") (pinfunction "PTD12_34") (pintype "passive"))
    )
    (net (code "118") (name "unconnected-(IC2B-PTD13-Pad35)") (class "Default")
      (node (ref "IC2") (pin "35") (pinfunction "PTD13_35") (pintype "passive"))
    )
    (net (code "119") (name "unconnected-(IC2B-PTD14-Pad36)") (class "Default")
      (node (ref "IC2") (pin "36") (pinfunction "PTD14_36") (pintype "passive"))
    )
    (net (code "120") (name "unconnected-(IC2B-PTD15-Pad37)") (class "Default")
      (node (ref "IC2") (pin "37") (pinfunction "PTD15_37") (pintype "passive"))
    )
    (net (code "121") (name "unconnected-(IC2B-USB0_DM-Pad51)") (class "Default")
      (node (ref "IC2") (pin "51") (pinfunction "USB0_DM_51") (pintype "passive"))
    )
    (net (code "122") (name "unconnected-(IC2B-USB0_DP-Pad52)") (class "Default")
      (node (ref "IC2") (pin "52") (pinfunction "USB0_DP_52") (pintype "passive"))
    )
    (net (code "123") (name "unconnected-(IC2C-3V3-Pad61)") (class "Default")
      (node (ref "IC2") (pin "61") (pinfunction "3V3_61") (pintype "passive"))
    )
    (net (code "124") (name "unconnected-(IC2C-ADC0_DM0-Pad57)") (class "Default")
      (node (ref "IC2") (pin "57") (pinfunction "ADC0_DM0_57") (pintype "passive"))
    )
    (net (code "125") (name "unconnected-(IC2C-ADC0_DM3-Pad59)") (class "Default")
      (node (ref "IC2") (pin "59") (pinfunction "ADC0_DM3_59") (pintype "passive"))
    )
    (net (code "126") (name "unconnected-(IC2C-ADC0_DP0-Pad58)") (class "Default")
      (node (ref "IC2") (pin "58") (pinfunction "ADC0_DP0_58") (pintype "passive"))
    )
    (net (code "127") (name "unconnected-(IC2C-ADC0_DP3-Pad60)") (class "Default")
      (node (ref "IC2") (pin "60") (pinfunction "ADC0_DP3_60") (pintype "passive"))
    )
    (net (code "128") (name "unconnected-(IC2C-ADC0_SE16-Pad63)") (class "Default")
      (node (ref "IC2") (pin "63") (pinfunction "ADC0_SE16_63") (pintype "passive"))
    )
    (net (code "129") (name "unconnected-(IC2C-ADC1_SE16-Pad64)") (class "Default")
      (node (ref "IC2") (pin "64") (pinfunction "ADC1_SE16_64") (pintype "passive"))
    )
    (net (code "130") (name "unconnected-(IC2C-DAC0_OUT-Pad65)") (class "Default")
      (node (ref "IC2") (pin "65") (pinfunction "DAC0_OUT_65") (pintype "passive"))
    )
    (net (code "131") (name "unconnected-(IC2C-DAC1_OUT-Pad66)") (class "Default")
      (node (ref "IC2") (pin "66") (pinfunction "DAC1_OUT_66") (pintype "passive"))
    )
    (net (code "132") (name "unconnected-(IC2C-PTA5-Pad72)") (class "Default")
      (node (ref "IC2") (pin "72") (pinfunction "PTA5_72") (pintype "passive"))
    )
    (net (code "133") (name "unconnected-(IC2C-PTA6-Pad73)") (class "Default")
      (node (ref "IC2") (pin "73") (pinfunction "PTA6_73") (pintype "passive"))
    )
    (net (code "134") (name "unconnected-(IC2C-PTA7-Pad74)") (class "Default")
      (node (ref "IC2") (pin "74") (pinfunction "PTA7_74") (pintype "passive"))
    )
    (net (code "135") (name "unconnected-(IC2C-PTA8-Pad75)") (class "Default")
      (node (ref "IC2") (pin "75") (pinfunction "PTA8_75") (pintype "passive"))
    )
    (net (code "136") (name "unconnected-(IC2C-PTA9-Pad76)") (class "Default")
      (node (ref "IC2") (pin "76") (pinfunction "PTA9_76") (pintype "passive"))
    )
    (net (code "137") (name "unconnected-(IC2C-PTA19-Pad85)") (class "Default")
      (node (ref "IC2") (pin "85") (pinfunction "PTA19_85") (pintype "passive"))
    )
    (net (code "138") (name "unconnected-(IC2C-PTA24-Pad86)") (class "Default")
      (node (ref "IC2") (pin "86") (pinfunction "PTA24_86") (pintype "passive"))
    )
    (net (code "139") (name "unconnected-(IC2C-PTE28-Pad71)") (class "Default")
      (node (ref "IC2") (pin "71") (pinfunction "PTE28_71") (pintype "passive"))
    )
    (net (code "140") (name "unconnected-(IC2C-VREFH-Pad62)") (class "Default")
      (node (ref "IC2") (pin "62") (pinfunction "VREFH_62") (pintype "passive"))
    )
    (net (code "141") (name "unconnected-(IC2D-PTB8-Pad100)") (class "Default")
      (node (ref "IC2") (pin "100") (pinfunction "PTB8_100") (pintype "passive"))
    )
    (net (code "142") (name "unconnected-(IC2D-PTB9-Pad101)") (class "Default")
      (node (ref "IC2") (pin "101") (pinfunction "PTB9_101") (pintype "passive"))
    )
    (net (code "143") (name "unconnected-(IC2D-PTB10-Pad103)") (class "Default")
      (node (ref "IC2") (pin "103") (pinfunction "PTB10_103") (pintype "passive"))
    )
    (net (code "144") (name "unconnected-(IC2D-PTB11-Pad102)") (class "Default")
      (node (ref "IC2") (pin "102") (pinfunction "PTB11_102") (pintype "passive"))
    )
    (net (code "145") (name "unconnected-(IC2D-PTB16-Pad105)") (class "Default")
      (node (ref "IC2") (pin "105") (pinfunction "PTB16_105") (pintype "passive"))
    )
    (net (code "146") (name "unconnected-(IC2D-PTB17-Pad104)") (class "Default")
      (node (ref "IC2") (pin "104") (pinfunction "PTB17_104") (pintype "passive"))
    )
    (net (code "147") (name "unconnected-(IC2D-PTB18-Pad107)") (class "Default")
      (node (ref "IC2") (pin "107") (pinfunction "PTB18_107") (pintype "passive"))
    )
    (net (code "148") (name "unconnected-(IC2D-PTB19-Pad106)") (class "Default")
      (node (ref "IC2") (pin "106") (pinfunction "PTB19_106") (pintype "passive"))
    )
    (net (code "149") (name "unconnected-(IC2D-PTB20-Pad109)") (class "Default")
      (node (ref "IC2") (pin "109") (pinfunction "PTB20_109") (pintype "passive"))
    )
    (net (code "150") (name "unconnected-(IC2D-PTB21-Pad108)") (class "Default")
      (node (ref "IC2") (pin "108") (pinfunction "PTB21_108") (pintype "passive"))
    )
    (net (code "151") (name "unconnected-(IC2D-PTB22-Pad111)") (class "Default")
      (node (ref "IC2") (pin "111") (pinfunction "PTB22_111") (pintype "passive"))
    )
    (net (code "152") (name "unconnected-(IC2D-PTB23-Pad110)") (class "Default")
      (node (ref "IC2") (pin "110") (pinfunction "PTB23_110") (pintype "passive"))
    )
    (net (code "153") (name "unconnected-(IC2D-PTC0-Pad112)") (class "Default")
      (node (ref "IC2") (pin "112") (pinfunction "PTC0_112") (pintype "passive"))
    )
    (net (code "154") (name "unconnected-(IC2E-3V3-Pad122)") (class "Default")
      (node (ref "IC2") (pin "122") (pinfunction "3V3_122") (pintype "passive"))
    )
    (net (code "155") (name "unconnected-(IC2E-5V-Pad116)") (class "Default")
      (node (ref "IC2") (pin "116") (pinfunction "5V_116") (pintype "passive"))
    )
    (net (code "156") (name "unconnected-(IC2E-A0-Pad119)") (class "Default")
      (node (ref "IC2") (pin "119") (pinfunction "A0_119") (pintype "passive"))
    )
    (net (code "157") (name "unconnected-(IC2E-A1-Pad115)") (class "Default")
      (node (ref "IC2") (pin "115") (pinfunction "A1_115") (pintype "passive"))
    )
    (net (code "158") (name "unconnected-(IC2E-A2-Pad117)") (class "Default")
      (node (ref "IC2") (pin "117") (pinfunction "A2_117") (pintype "passive"))
    )
    (net (code "159") (name "unconnected-(IC2E-A3-Pad121)") (class "Default")
      (node (ref "IC2") (pin "121") (pinfunction "A3_121") (pintype "passive"))
    )
    (net (code "160") (name "unconnected-(IC2E-A4-Pad120)") (class "Default")
      (node (ref "IC2") (pin "120") (pinfunction "A4_120") (pintype "passive"))
    )
    (net (code "161") (name "unconnected-(IC2E-GND-Pad114)") (class "Default")
      (node (ref "IC2") (pin "114") (pinfunction "GND_114") (pintype "passive"))
    )
    (net (code "162") (name "unconnected-(IC2E-GND-Pad118)") (class "Default")
      (node (ref "IC2") (pin "118") (pinfunction "GND_118") (pintype "passive"))
    )
    (net (code "163") (name "unconnected-(IC2E-RES-Pad113)") (class "Default")
      (node (ref "IC2") (pin "113") (pinfunction "RES_113") (pintype "passive"))
    )
    (net (code "164") (name "unconnected-(JP4-Pad5)") (class "Default")
      (node (ref "JP4") (pin "5") (pinfunction "5_5") (pintype "passive"))
    )
    (net (code "165") (name "unconnected-(JP4-Pad6)") (class "Default")
      (node (ref "JP4") (pin "6") (pinfunction "6_6") (pintype "passive"))
    )
    (net (code "166") (name "unconnected-(JP5-Pad5)") (class "Default")
      (node (ref "JP5") (pin "5") (pinfunction "5_5") (pintype "passive"))
    )
    (net (code "167") (name "unconnected-(JP5-Pad6)") (class "Default")
      (node (ref "JP5") (pin "6") (pinfunction "6_6") (pintype "passive"))
    )
    (net (code "168") (name "unconnected-(P8-F3-Pad6)") (class "Default")
      (node (ref "P8") (pin "6") (pinfunction "F3_6") (pintype "passive"))
    )
    (net (code "169") (name "unconnected-(P8-FO-Pad14)") (class "Default")
      (node (ref "P8") (pin "14") (pinfunction "FO_14") (pintype "passive"))
    )
    (net (code "170") (name "unconnected-(P8-LE-Pad10)") (class "Default")
      (node (ref "P8") (pin "10") (pinfunction "LE_10") (pintype "passive"))
    )
    (net (code "171") (name "unconnected-(P8-OE-Pad4)") (class "Default")
      (node (ref "P8") (pin "4") (pinfunction "OE_4") (pintype "passive"))
    )
    (net (code "172") (name "unconnected-(P8-PW-Pad16)") (class "Default")
      (node (ref "P8") (pin "16") (pinfunction "PW_16") (pintype "passive"))
    )
  )
)
